# GR_Action_Ascensseur.net
KiCad netlist of a schematic drawn in Altium Designer
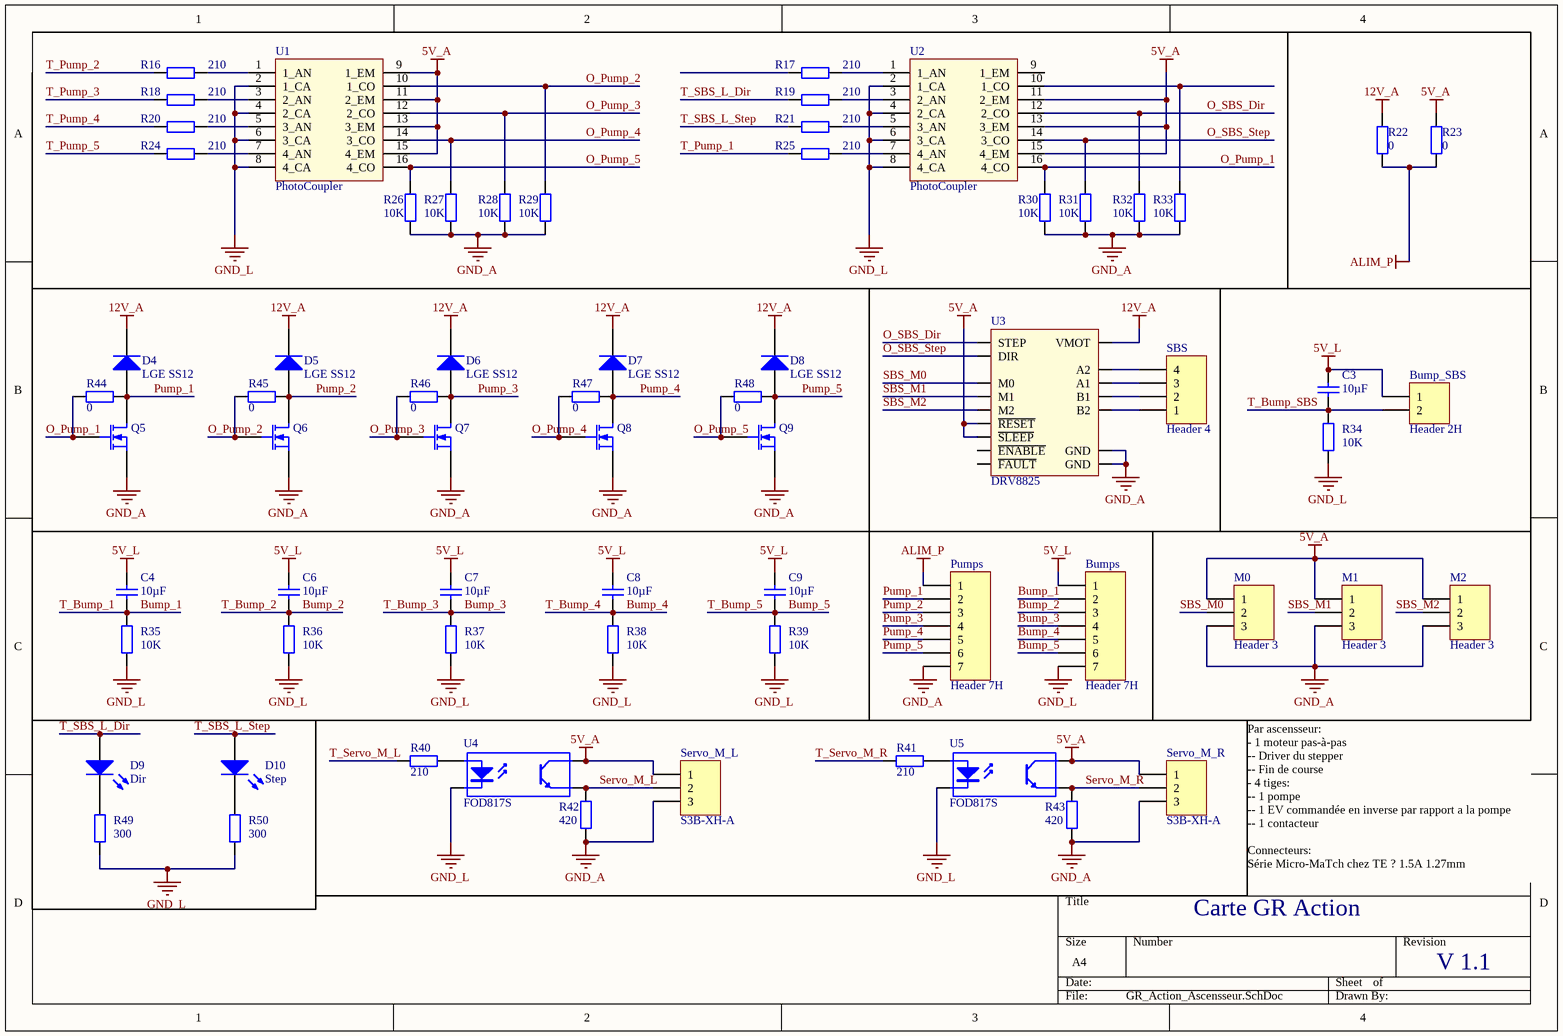
[diagram p0: GR_Action_Ascensseur.SchDoc]

(export (version "E")
  (design (tool "Eeschema 10.0.6"))
  (components
    (comp (ref "Bumps")
      (value "Header 7H")
      (footprint "S7B-XH-A")
      (description "Header, 7-Pin, Right Angle")
      (fields (field (name "PUBLISHER") "Altium Limited"))
      (libsource (lib "Miscellaneous Connectors") (part "Header 7H"))
    )
    (comp (ref "Bump_SBS")
      (value "Header 2H")
      (footprint "S2B-XH-A")
      (description "Header, 2-Pin, Right Angle")
      (fields (field (name "PUBLISHER") "Altium Limited"))
      (libsource (lib "Miscellaneous Connectors") (part "Header 2H"))
    )
    (comp (ref "C3")
      (value "10µF")
      (footprint "Capacitor 1206")
      (description "Capacitor")
      (fields (field (name "PUBLISHER") "Altium Limited"))
      (libsource (lib "Miscellaneous Devices") (part "Cap"))
    )
    (comp (ref "C4")
      (value "10µF")
      (footprint "Capacitor 1206")
      (description "Capacitor")
      (fields (field (name "PUBLISHER") "Altium Limited"))
      (libsource (lib "Miscellaneous Devices") (part "Cap"))
    )
    (comp (ref "C6")
      (value "10µF")
      (footprint "Capacitor 1206")
      (description "Capacitor")
      (fields (field (name "PUBLISHER") "Altium Limited"))
      (libsource (lib "Miscellaneous Devices") (part "Cap"))
    )
    (comp (ref "C7")
      (value "10µF")
      (footprint "Capacitor 1206")
      (description "Capacitor")
      (fields (field (name "PUBLISHER") "Altium Limited"))
      (libsource (lib "Miscellaneous Devices") (part "Cap"))
    )
    (comp (ref "C8")
      (value "10µF")
      (footprint "Capacitor 1206")
      (description "Capacitor")
      (fields (field (name "PUBLISHER") "Altium Limited"))
      (libsource (lib "Miscellaneous Devices") (part "Cap"))
    )
    (comp (ref "C9")
      (value "10µF")
      (footprint "Capacitor 1206")
      (description "Capacitor")
      (fields (field (name "PUBLISHER") "Altium Limited"))
      (libsource (lib "Miscellaneous Devices") (part "Cap"))
    )
    (comp (ref "D4")
      (value "LGE SS12")
      (footprint "SMB")
      (description "Default Diode")
      (fields (field (name "PUBLISHER") "Altium Limited"))
      (libsource (lib "Miscellaneous Devices") (part "Diode"))
    )
    (comp (ref "D5")
      (value "LGE SS12")
      (footprint "SMB")
      (description "Default Diode")
      (fields (field (name "PUBLISHER") "Altium Limited"))
      (libsource (lib "Miscellaneous Devices") (part "Diode"))
    )
    (comp (ref "D6")
      (value "LGE SS12")
      (footprint "SMB")
      (description "Default Diode")
      (fields (field (name "PUBLISHER") "Altium Limited"))
      (libsource (lib "Miscellaneous Devices") (part "Diode"))
    )
    (comp (ref "D7")
      (value "LGE SS12")
      (footprint "SMB")
      (description "Default Diode")
      (fields (field (name "PUBLISHER") "Altium Limited"))
      (libsource (lib "Miscellaneous Devices") (part "Diode"))
    )
    (comp (ref "D8")
      (value "LGE SS12")
      (footprint "SMB")
      (description "Default Diode")
      (fields (field (name "PUBLISHER") "Altium Limited"))
      (libsource (lib "Miscellaneous Devices") (part "Diode"))
    )
    (comp (ref "D9")
      (value "Dir")
      (footprint "KP-3216SEC")
      (description "Typical RED, GREEN, YELLOW, AMBER GaAs LED")
      (fields (field (name "PUBLISHER") "Altium Limited"))
      (libsource (lib "Miscellaneous Devices") (part "LED2"))
    )
    (comp (ref "D10")
      (value "Step")
      (footprint "KP-3216SEC")
      (description "Typical RED, GREEN, YELLOW, AMBER GaAs LED")
      (fields (field (name "PUBLISHER") "Altium Limited"))
      (libsource (lib "Miscellaneous Devices") (part "LED2"))
    )
    (comp (ref "M0")
      (value "Header 3")
      (footprint "HDR1X3")
      (description "Header, 3-Pin")
      (fields (field (name "PUBLISHER") "Altium Limited"))
      (libsource (lib "Miscellaneous Connectors") (part "Header 3"))
    )
    (comp (ref "M1")
      (value "Header 3")
      (footprint "HDR1X3")
      (description "Header, 3-Pin")
      (fields (field (name "PUBLISHER") "Altium Limited"))
      (libsource (lib "Miscellaneous Connectors") (part "Header 3"))
    )
    (comp (ref "M2")
      (value "Header 3")
      (footprint "HDR1X3")
      (description "Header, 3-Pin")
      (fields (field (name "PUBLISHER") "Altium Limited"))
      (libsource (lib "Miscellaneous Connectors") (part "Header 3"))
    )
    (comp (ref "Pumps")
      (value "Header 7H")
      (footprint "S7B-XH-A")
      (description "Header, 7-Pin, Right Angle")
      (fields (field (name "PUBLISHER") "Altium Limited"))
      (libsource (lib "Miscellaneous Connectors") (part "Header 7H"))
    )
    (comp (ref "Q5")
      (value "MOSFET-N")
      (footprint "SOT23_M")
      (description "N-Channel MOSFET")
      (fields (field (name "PUBLISHER") "Altium Limited"))
      (libsource (lib "Miscellaneous Devices") (part "MOSFET-N"))
    )
    (comp (ref "Q6")
      (value "MOSFET-N")
      (footprint "SOT23_M")
      (description "N-Channel MOSFET")
      (fields (field (name "PUBLISHER") "Altium Limited"))
      (libsource (lib "Miscellaneous Devices") (part "MOSFET-N"))
    )
    (comp (ref "Q7")
      (value "MOSFET-N")
      (footprint "SOT23_M")
      (description "N-Channel MOSFET")
      (fields (field (name "PUBLISHER") "Altium Limited"))
      (libsource (lib "Miscellaneous Devices") (part "MOSFET-N"))
    )
    (comp (ref "Q8")
      (value "MOSFET-N")
      (footprint "SOT23_M")
      (description "N-Channel MOSFET")
      (fields (field (name "PUBLISHER") "Altium Limited"))
      (libsource (lib "Miscellaneous Devices") (part "MOSFET-N"))
    )
    (comp (ref "Q9")
      (value "MOSFET-N")
      (footprint "SOT23_M")
      (description "N-Channel MOSFET")
      (fields (field (name "PUBLISHER") "Altium Limited"))
      (libsource (lib "Miscellaneous Devices") (part "MOSFET-N"))
    )
    (comp (ref "R16")
      (value "210")
      (footprint "Resistor 1206")
      (description "Resistor")
      (fields (field (name "Comment") "Res2") (field (name "PUBLISHER") "Altium Limited"))
      (libsource (lib "") (part "Res2_2"))
    )
    (comp (ref "R17")
      (value "210")
      (footprint "Resistor 1206")
      (description "Resistor")
      (fields (field (name "Comment") "Res2") (field (name "PUBLISHER") "Altium Limited"))
      (libsource (lib "") (part "Res2_2"))
    )
    (comp (ref "R18")
      (value "210")
      (footprint "Resistor 1206")
      (description "Resistor")
      (fields (field (name "Comment") "Res2") (field (name "PUBLISHER") "Altium Limited"))
      (libsource (lib "") (part "Res2_2"))
    )
    (comp (ref "R19")
      (value "210")
      (footprint "Resistor 1206")
      (description "Resistor")
      (fields (field (name "Comment") "Res2") (field (name "PUBLISHER") "Altium Limited"))
      (libsource (lib "") (part "Res2_2"))
    )
    (comp (ref "R20")
      (value "210")
      (footprint "Resistor 1206")
      (description "Resistor")
      (fields (field (name "Comment") "Res2") (field (name "PUBLISHER") "Altium Limited"))
      (libsource (lib "") (part "Res2_2"))
    )
    (comp (ref "R21")
      (value "210")
      (footprint "Resistor 1206")
      (description "Resistor")
      (fields (field (name "Comment") "Res2") (field (name "PUBLISHER") "Altium Limited"))
      (libsource (lib "") (part "Res2_2"))
    )
    (comp (ref "R22")
      (value "0")
      (footprint "Resistor 1206")
      (description "Resistor")
      (fields (field (name "Comment") "Res2") (field (name "PUBLISHER") "Altium Limited"))
      (libsource (lib "") (part "Res2_1"))
    )
    (comp (ref "R23")
      (value "0")
      (footprint "Resistor 1206")
      (description "Resistor")
      (fields (field (name "Comment") "Res2") (field (name "PUBLISHER") "Altium Limited"))
      (libsource (lib "") (part "Res2_1"))
    )
    (comp (ref "R24")
      (value "210")
      (footprint "Resistor 1206")
      (description "Resistor")
      (fields (field (name "Comment") "Res2") (field (name "PUBLISHER") "Altium Limited"))
      (libsource (lib "") (part "Res2_2"))
    )
    (comp (ref "R25")
      (value "210")
      (footprint "Resistor 1206")
      (description "Resistor")
      (fields (field (name "Comment") "Res2") (field (name "PUBLISHER") "Altium Limited"))
      (libsource (lib "") (part "Res2_2"))
    )
    (comp (ref "R26")
      (value "10K")
      (footprint "Resistor 1206")
      (description "Resistor")
      (fields (field (name "Comment") "Res2") (field (name "PUBLISHER") "Altium Limited"))
      (libsource (lib "") (part "Res2_3"))
    )
    (comp (ref "R27")
      (value "10K")
      (footprint "Resistor 1206")
      (description "Resistor")
      (fields (field (name "Comment") "Res2") (field (name "PUBLISHER") "Altium Limited"))
      (libsource (lib "") (part "Res2_3"))
    )
    (comp (ref "R28")
      (value "10K")
      (footprint "Resistor 1206")
      (description "Resistor")
      (fields (field (name "Comment") "Res2") (field (name "PUBLISHER") "Altium Limited"))
      (libsource (lib "") (part "Res2_3"))
    )
    (comp (ref "R29")
      (value "10K")
      (footprint "Resistor 1206")
      (description "Resistor")
      (fields (field (name "Comment") "Res2") (field (name "PUBLISHER") "Altium Limited"))
      (libsource (lib "") (part "Res2_3"))
    )
    (comp (ref "R30")
      (value "10K")
      (footprint "Resistor 1206")
      (description "Resistor")
      (fields (field (name "Comment") "Res2") (field (name "PUBLISHER") "Altium Limited"))
      (libsource (lib "") (part "Res2_3"))
    )
    (comp (ref "R31")
      (value "10K")
      (footprint "Resistor 1206")
      (description "Resistor")
      (fields (field (name "Comment") "Res2") (field (name "PUBLISHER") "Altium Limited"))
      (libsource (lib "") (part "Res2_3"))
    )
    (comp (ref "R32")
      (value "10K")
      (footprint "Resistor 1206")
      (description "Resistor")
      (fields (field (name "Comment") "Res2") (field (name "PUBLISHER") "Altium Limited"))
      (libsource (lib "") (part "Res2_3"))
    )
    (comp (ref "R33")
      (value "10K")
      (footprint "Resistor 1206")
      (description "Resistor")
      (fields (field (name "Comment") "Res2") (field (name "PUBLISHER") "Altium Limited"))
      (libsource (lib "") (part "Res2_3"))
    )
    (comp (ref "R34")
      (value "10K")
      (footprint "Resistor 1206")
      (description "Resistor")
      (fields (field (name "Comment") "Res2") (field (name "PUBLISHER") "Altium Limited"))
      (libsource (lib "") (part "Res2_3"))
    )
    (comp (ref "R35")
      (value "10K")
      (footprint "Resistor 1206")
      (description "Resistor")
      (fields (field (name "Comment") "Res2") (field (name "PUBLISHER") "Altium Limited"))
      (libsource (lib "") (part "Res2_3"))
    )
    (comp (ref "R36")
      (value "10K")
      (footprint "Resistor 1206")
      (description "Resistor")
      (fields (field (name "Comment") "Res2") (field (name "PUBLISHER") "Altium Limited"))
      (libsource (lib "") (part "Res2_3"))
    )
    (comp (ref "R37")
      (value "10K")
      (footprint "Resistor 1206")
      (description "Resistor")
      (fields (field (name "Comment") "Res2") (field (name "PUBLISHER") "Altium Limited"))
      (libsource (lib "") (part "Res2_3"))
    )
    (comp (ref "R38")
      (value "10K")
      (footprint "Resistor 1206")
      (description "Resistor")
      (fields (field (name "Comment") "Res2") (field (name "PUBLISHER") "Altium Limited"))
      (libsource (lib "") (part "Res2_3"))
    )
    (comp (ref "R39")
      (value "10K")
      (footprint "Resistor 1206")
      (description "Resistor")
      (fields (field (name "Comment") "Res2") (field (name "PUBLISHER") "Altium Limited"))
      (libsource (lib "") (part "Res2_3"))
    )
    (comp (ref "R40")
      (value "210")
      (footprint "Resistor 1206")
      (description "Resistor")
      (fields (field (name "Comment") "Res2") (field (name "PUBLISHER") "Altium Limited"))
      (libsource (lib "") (part "Res2_2"))
    )
    (comp (ref "R41")
      (value "210")
      (footprint "Resistor 1206")
      (description "Resistor")
      (fields (field (name "Comment") "Res2") (field (name "PUBLISHER") "Altium Limited"))
      (libsource (lib "") (part "Res2_2"))
    )
    (comp (ref "R42")
      (value "420")
      (footprint "Resistor 1206")
      (description "Resistor")
      (fields (field (name "Comment") "Res2") (field (name "PUBLISHER") "Altium Limited"))
      (libsource (lib "") (part "Res2_3"))
    )
    (comp (ref "R43")
      (value "420")
      (footprint "Resistor 1206")
      (description "Resistor")
      (fields (field (name "Comment") "Res2") (field (name "PUBLISHER") "Altium Limited"))
      (libsource (lib "") (part "Res2_3"))
    )
    (comp (ref "R44")
      (value "0")
      (footprint "Resistor 1206")
      (description "Resistor")
      (fields (field (name "Comment") "Res2") (field (name "PUBLISHER") "Altium Limited"))
      (libsource (lib "Miscellaneous Devices") (part "Res2"))
    )
    (comp (ref "R45")
      (value "0")
      (footprint "Resistor 1206")
      (description "Resistor")
      (fields (field (name "Comment") "Res2") (field (name "PUBLISHER") "Altium Limited"))
      (libsource (lib "Miscellaneous Devices") (part "Res2"))
    )
    (comp (ref "R46")
      (value "0")
      (footprint "Resistor 1206")
      (description "Resistor")
      (fields (field (name "Comment") "Res2") (field (name "PUBLISHER") "Altium Limited"))
      (libsource (lib "Miscellaneous Devices") (part "Res2"))
    )
    (comp (ref "R47")
      (value "0")
      (footprint "Resistor 1206")
      (description "Resistor")
      (fields (field (name "Comment") "Res2") (field (name "PUBLISHER") "Altium Limited"))
      (libsource (lib "Miscellaneous Devices") (part "Res2"))
    )
    (comp (ref "R48")
      (value "0")
      (footprint "Resistor 1206")
      (description "Resistor")
      (fields (field (name "Comment") "Res2") (field (name "PUBLISHER") "Altium Limited"))
      (libsource (lib "Miscellaneous Devices") (part "Res2"))
    )
    (comp (ref "R49")
      (value "300")
      (footprint "Resistor 1206")
      (description "Resistor")
      (fields (field (name "Comment") "Res2") (field (name "PUBLISHER") "Altium Limited"))
      (libsource (lib "") (part "Res2_3"))
    )
    (comp (ref "R50")
      (value "300")
      (footprint "Resistor 1206")
      (description "Resistor")
      (fields (field (name "Comment") "Res2") (field (name "PUBLISHER") "Altium Limited"))
      (libsource (lib "") (part "Res2_3"))
    )
    (comp (ref "SBS")
      (value "Header 4")
      (footprint "S4B-XH-A")
      (description "Header, 4-Pin")
      (fields (field (name "PUBLISHER") "Altium Limited"))
      (libsource (lib "Miscellaneous Connectors") (part "Header 4"))
    )
    (comp (ref "Servo_M_L")
      (value "S3B-XH-A")
      (footprint "S3B-XH-A")
      (description "Header, 3-Pin, Right Angle")
      (fields (field (name "PUBLISHER") "Altium Limited"))
      (libsource (lib "Miscellaneous Connectors") (part "Header 3H"))
    )
    (comp (ref "Servo_M_R")
      (value "S3B-XH-A")
      (footprint "S3B-XH-A")
      (description "Header, 3-Pin, Right Angle")
      (fields (field (name "PUBLISHER") "Altium Limited"))
      (libsource (lib "Miscellaneous Connectors") (part "Header 3H"))
    )
    (comp (ref "U1")
      (value "PhotoCoupler")
      (footprint "LTV-247")
      (description "Integrated Circuit")
      (fields
        (field (name "MANUFACTURER_PART_NUMBER") "LTV-247")
        (field (name "MOUSER PART NUMBER") "859-LTV-247")
      )
      (libsource (lib "SamacSys") (part "LTV-247"))
    )
    (comp (ref "U2")
      (value "PhotoCoupler")
      (footprint "LTV-247")
      (description "Integrated Circuit")
      (fields
        (field (name "MANUFACTURER_PART_NUMBER") "LTV-247")
        (field (name "MOUSER PART NUMBER") "859-LTV-247")
      )
      (libsource (lib "SamacSys") (part "LTV-247"))
    )
    (comp (ref "U3")
      (value "DRV8825")
      (footprint "DRV8825")
      (description "Stepper Driver Module")
      (libsource (lib "SupaeroRobot") (part "DRV8825"))
    )
    (comp (ref "U4")
      (value "FOD817S")
      (footprint "SOP254P1016X385-4N")
      (description "4-Pin Phototransistor Optocoupler")
      (fields (field (name "PUBLISHER") "Altium Limited"))
      (libsource (lib "Miscellaneous Devices") (part "Optoisolator1"))
    )
    (comp (ref "U5")
      (value "FOD817S")
      (footprint "SOP254P1016X385-4N")
      (description "4-Pin Phototransistor Optocoupler")
      (fields (field (name "PUBLISHER") "Altium Limited"))
      (libsource (lib "Miscellaneous Devices") (part "Optoisolator1"))
    )
  )
  (nets
    (net (code "1") (name "/Bump_1") (class "Default")
      (node (ref "Bumps") (pin "2") (pinfunction "2_2") (pintype "passive"))
      (node (ref "C4") (pin "1") (pinfunction "1_1") (pintype "passive"))
      (node (ref "R35") (pin "2") (pinfunction "2_2") (pintype "passive"))
    )
    (net (code "2") (name "/Bump_2") (class "Default")
      (node (ref "Bumps") (pin "3") (pinfunction "3_3") (pintype "passive"))
      (node (ref "C6") (pin "1") (pinfunction "1_1") (pintype "passive"))
      (node (ref "R36") (pin "2") (pinfunction "2_2") (pintype "passive"))
    )
    (net (code "3") (name "/Bump_3") (class "Default")
      (node (ref "Bumps") (pin "4") (pinfunction "4_4") (pintype "passive"))
      (node (ref "C7") (pin "1") (pinfunction "1_1") (pintype "passive"))
      (node (ref "R37") (pin "2") (pinfunction "2_2") (pintype "passive"))
    )
    (net (code "4") (name "/Bump_4") (class "Default")
      (node (ref "Bumps") (pin "5") (pinfunction "5_5") (pintype "passive"))
      (node (ref "C8") (pin "1") (pinfunction "1_1") (pintype "passive"))
      (node (ref "R38") (pin "2") (pinfunction "2_2") (pintype "passive"))
    )
    (net (code "5") (name "/Bump_5") (class "Default")
      (node (ref "Bumps") (pin "6") (pinfunction "6_6") (pintype "passive"))
      (node (ref "C9") (pin "1") (pinfunction "1_1") (pintype "passive"))
      (node (ref "R39") (pin "2") (pinfunction "2_2") (pintype "passive"))
    )
    (net (code "6") (name "/O_Pump_1") (class "Default")
      (node (ref "Q5") (pin "2") (pinfunction "G_2") (pintype "passive"))
      (node (ref "R30") (pin "2") (pinfunction "2_2") (pintype "passive"))
      (node (ref "R44") (pin "1") (pinfunction "1_1") (pintype "passive"))
      (node (ref "U2") (pin "16") (pinfunction "4_CO_16") (pintype "passive"))
    )
    (net (code "7") (name "/O_Pump_2") (class "Default")
      (node (ref "Q6") (pin "2") (pinfunction "G_2") (pintype "passive"))
      (node (ref "R29") (pin "2") (pinfunction "2_2") (pintype "passive"))
      (node (ref "R45") (pin "1") (pinfunction "1_1") (pintype "passive"))
      (node (ref "U1") (pin "10") (pinfunction "1_CO_10") (pintype "passive"))
    )
    (net (code "8") (name "/O_Pump_3") (class "Default")
      (node (ref "Q7") (pin "2") (pinfunction "G_2") (pintype "passive"))
      (node (ref "R28") (pin "2") (pinfunction "2_2") (pintype "passive"))
      (node (ref "R46") (pin "1") (pinfunction "1_1") (pintype "passive"))
      (node (ref "U1") (pin "12") (pinfunction "2_CO_12") (pintype "passive"))
    )
    (net (code "9") (name "/O_Pump_4") (class "Default")
      (node (ref "Q8") (pin "2") (pinfunction "G_2") (pintype "passive"))
      (node (ref "R27") (pin "2") (pinfunction "2_2") (pintype "passive"))
      (node (ref "R47") (pin "1") (pinfunction "1_1") (pintype "passive"))
      (node (ref "U1") (pin "14") (pinfunction "3_CO_14") (pintype "passive"))
    )
    (net (code "10") (name "/O_Pump_5") (class "Default")
      (node (ref "Q9") (pin "2") (pinfunction "G_2") (pintype "passive"))
      (node (ref "R26") (pin "2") (pinfunction "2_2") (pintype "passive"))
      (node (ref "R48") (pin "1") (pinfunction "1_1") (pintype "passive"))
      (node (ref "U1") (pin "16") (pinfunction "4_CO_16") (pintype "passive"))
    )
    (net (code "11") (name "/O_SBS_Dir") (class "Default")
      (node (ref "R32") (pin "2") (pinfunction "2_2") (pintype "passive"))
      (node (ref "U2") (pin "12") (pinfunction "2_CO_12") (pintype "passive"))
      (node (ref "U3") (pin "7") (pinfunction "STEP_7") (pintype "passive"))
    )
    (net (code "12") (name "/O_SBS_Step") (class "Default")
      (node (ref "R31") (pin "2") (pinfunction "2_2") (pintype "passive"))
      (node (ref "U2") (pin "14") (pinfunction "3_CO_14") (pintype "passive"))
      (node (ref "U3") (pin "8") (pinfunction "DIR_8") (pintype "passive"))
    )
    (net (code "13") (name "/Pump_1") (class "Default")
      (node (ref "D4") (pin "1") (pinfunction "A_1") (pintype "passive"))
      (node (ref "Pumps") (pin "2") (pinfunction "2_2") (pintype "passive"))
      (node (ref "Q5") (pin "1") (pinfunction "D_1") (pintype "passive"))
      (node (ref "R44") (pin "2") (pinfunction "2_2") (pintype "passive"))
    )
    (net (code "14") (name "/Pump_2") (class "Default")
      (node (ref "D5") (pin "1") (pinfunction "A_1") (pintype "passive"))
      (node (ref "Pumps") (pin "3") (pinfunction "3_3") (pintype "passive"))
      (node (ref "Q6") (pin "1") (pinfunction "D_1") (pintype "passive"))
      (node (ref "R45") (pin "2") (pinfunction "2_2") (pintype "passive"))
    )
    (net (code "15") (name "/Pump_3") (class "Default")
      (node (ref "D6") (pin "1") (pinfunction "A_1") (pintype "passive"))
      (node (ref "Pumps") (pin "4") (pinfunction "4_4") (pintype "passive"))
      (node (ref "Q7") (pin "1") (pinfunction "D_1") (pintype "passive"))
      (node (ref "R46") (pin "2") (pinfunction "2_2") (pintype "passive"))
    )
    (net (code "16") (name "/Pump_4") (class "Default")
      (node (ref "D7") (pin "1") (pinfunction "A_1") (pintype "passive"))
      (node (ref "Pumps") (pin "5") (pinfunction "5_5") (pintype "passive"))
      (node (ref "Q8") (pin "1") (pinfunction "D_1") (pintype "passive"))
      (node (ref "R47") (pin "2") (pinfunction "2_2") (pintype "passive"))
    )
    (net (code "17") (name "/Pump_5") (class "Default")
      (node (ref "D8") (pin "1") (pinfunction "A_1") (pintype "passive"))
      (node (ref "Pumps") (pin "6") (pinfunction "6_6") (pintype "passive"))
      (node (ref "Q9") (pin "1") (pinfunction "D_1") (pintype "passive"))
      (node (ref "R48") (pin "2") (pinfunction "2_2") (pintype "passive"))
    )
    (net (code "18") (name "/SBS_M0") (class "Default")
      (node (ref "M0") (pin "2") (pinfunction "2_2") (pintype "passive"))
      (node (ref "U3") (pin "2") (pinfunction "M0_2") (pintype "passive"))
    )
    (net (code "19") (name "/SBS_M1") (class "Default")
      (node (ref "M1") (pin "2") (pinfunction "2_2") (pintype "passive"))
      (node (ref "U3") (pin "3") (pinfunction "M1_3") (pintype "passive"))
    )
    (net (code "20") (name "/SBS_M2") (class "Default")
      (node (ref "M2") (pin "2") (pinfunction "2_2") (pintype "passive"))
      (node (ref "U3") (pin "4") (pinfunction "M2_4") (pintype "passive"))
    )
    (net (code "21") (name "/Servo_M_L") (class "Default")
      (node (ref "R42") (pin "2") (pinfunction "2_2") (pintype "passive"))
      (node (ref "Servo_M_L") (pin "2") (pinfunction "2_2") (pintype "passive"))
      (node (ref "U4") (pin "3") (pinfunction "E_3") (pintype "passive"))
    )
    (net (code "22") (name "/Servo_M_R") (class "Default")
      (node (ref "R43") (pin "2") (pinfunction "2_2") (pintype "passive"))
      (node (ref "Servo_M_R") (pin "2") (pinfunction "2_2") (pintype "passive"))
      (node (ref "U5") (pin "3") (pinfunction "E_3") (pintype "passive"))
    )
    (net (code "23") (name "/T_Bump_SBS") (class "Default")
      (node (ref "Bump_SBS") (pin "2") (pinfunction "2_2") (pintype "passive"))
      (node (ref "C3") (pin "1") (pinfunction "1_1") (pintype "passive"))
      (node (ref "R34") (pin "2") (pinfunction "2_2") (pintype "passive"))
    )
    (net (code "24") (name "/T_Pump_1") (class "Default")
      (node (ref "R25") (pin "2") (pinfunction "2_2") (pintype "passive"))
    )
    (net (code "25") (name "/T_Pump_2") (class "Default")
      (node (ref "R16") (pin "2") (pinfunction "2_2") (pintype "passive"))
    )
    (net (code "26") (name "/T_Pump_3") (class "Default")
      (node (ref "R18") (pin "2") (pinfunction "2_2") (pintype "passive"))
    )
    (net (code "27") (name "/T_Pump_4") (class "Default")
      (node (ref "R20") (pin "2") (pinfunction "2_2") (pintype "passive"))
    )
    (net (code "28") (name "/T_Pump_5") (class "Default")
      (node (ref "R24") (pin "2") (pinfunction "2_2") (pintype "passive"))
    )
    (net (code "29") (name "/T_SBS_L_Dir") (class "Default")
      (node (ref "D9") (pin "1") (pinfunction "A_1") (pintype "passive"))
      (node (ref "R19") (pin "2") (pinfunction "2_2") (pintype "passive"))
    )
    (net (code "30") (name "/T_SBS_L_Step") (class "Default")
      (node (ref "D10") (pin "1") (pinfunction "A_1") (pintype "passive"))
      (node (ref "R21") (pin "2") (pinfunction "2_2") (pintype "passive"))
    )
    (net (code "31") (name "/T_Servo_M_L") (class "Default")
      (node (ref "R40") (pin "2") (pinfunction "2_2") (pintype "passive"))
    )
    (net (code "32") (name "/T_Servo_M_R") (class "Default")
      (node (ref "R41") (pin "2") (pinfunction "2_2") (pintype "passive"))
    )
    (net (code "33") (name "5V_A") (class "Default")
      (node (ref "M0") (pin "1") (pinfunction "1_1") (pintype "passive"))
      (node (ref "M1") (pin "1") (pinfunction "1_1") (pintype "passive"))
      (node (ref "M2") (pin "1") (pinfunction "1_1") (pintype "passive"))
      (node (ref "R23") (pin "1") (pinfunction "1_1") (pintype "passive"))
      (node (ref "Servo_M_L") (pin "1") (pinfunction "1_1") (pintype "passive"))
      (node (ref "Servo_M_R") (pin "1") (pinfunction "1_1") (pintype "passive"))
      (node (ref "U1") (pin "11") (pinfunction "2_EM_11") (pintype "passive"))
      (node (ref "U1") (pin "13") (pinfunction "3_EM_13") (pintype "passive"))
      (node (ref "U1") (pin "15") (pinfunction "4_EM_15") (pintype "passive"))
      (node (ref "U1") (pin "9") (pinfunction "1_EM_9") (pintype "passive"))
      (node (ref "U2") (pin "11") (pinfunction "2_EM_11") (pintype "passive"))
      (node (ref "U2") (pin "13") (pinfunction "3_EM_13") (pintype "passive"))
      (node (ref "U2") (pin "15") (pinfunction "4_EM_15") (pintype "passive"))
      (node (ref "U3") (pin "5") (pinfunction "~{RESET}_5") (pintype "passive"))
      (node (ref "U3") (pin "6") (pinfunction "~{SLEEP}_6") (pintype "passive"))
      (node (ref "U4") (pin "4") (pinfunction "C_4") (pintype "passive"))
      (node (ref "U5") (pin "4") (pinfunction "C_4") (pintype "passive"))
    )
    (net (code "34") (name "5V_L") (class "Default")
      (node (ref "Bump_SBS") (pin "1") (pinfunction "1_1") (pintype "passive"))
      (node (ref "Bumps") (pin "1") (pinfunction "1_1") (pintype "passive"))
      (node (ref "C3") (pin "2") (pinfunction "2_2") (pintype "passive"))
      (node (ref "C4") (pin "2") (pinfunction "2_2") (pintype "passive"))
      (node (ref "C6") (pin "2") (pinfunction "2_2") (pintype "passive"))
      (node (ref "C7") (pin "2") (pinfunction "2_2") (pintype "passive"))
      (node (ref "C8") (pin "2") (pinfunction "2_2") (pintype "passive"))
      (node (ref "C9") (pin "2") (pinfunction "2_2") (pintype "passive"))
    )
    (net (code "35") (name "12V_A") (class "Default")
      (node (ref "D4") (pin "2") (pinfunction "K_2") (pintype "passive"))
      (node (ref "D5") (pin "2") (pinfunction "K_2") (pintype "passive"))
      (node (ref "D6") (pin "2") (pinfunction "K_2") (pintype "passive"))
      (node (ref "D7") (pin "2") (pinfunction "K_2") (pintype "passive"))
      (node (ref "D8") (pin "2") (pinfunction "K_2") (pintype "passive"))
      (node (ref "R22") (pin "1") (pinfunction "1_1") (pintype "passive"))
      (node (ref "U3") (pin "16") (pinfunction "VMOT_16") (pintype "passive"))
    )
    (net (code "36") (name "ALIM_P") (class "Default")
      (node (ref "Pumps") (pin "1") (pinfunction "1_1") (pintype "passive"))
      (node (ref "R22") (pin "2") (pinfunction "2_2") (pintype "passive"))
      (node (ref "R23") (pin "2") (pinfunction "2_2") (pintype "passive"))
    )
    (net (code "37") (name "GND_A") (class "Default")
      (node (ref "M0") (pin "3") (pinfunction "3_3") (pintype "passive"))
      (node (ref "M1") (pin "3") (pinfunction "3_3") (pintype "passive"))
      (node (ref "M2") (pin "3") (pinfunction "3_3") (pintype "passive"))
      (node (ref "Pumps") (pin "7") (pinfunction "7_7") (pintype "passive"))
      (node (ref "Q5") (pin "3") (pinfunction "S_3") (pintype "passive"))
      (node (ref "Q6") (pin "3") (pinfunction "S_3") (pintype "passive"))
      (node (ref "Q7") (pin "3") (pinfunction "S_3") (pintype "passive"))
      (node (ref "Q8") (pin "3") (pinfunction "S_3") (pintype "passive"))
      (node (ref "Q9") (pin "3") (pinfunction "S_3") (pintype "passive"))
      (node (ref "R26") (pin "1") (pinfunction "1_1") (pintype "passive"))
      (node (ref "R27") (pin "1") (pinfunction "1_1") (pintype "passive"))
      (node (ref "R28") (pin "1") (pinfunction "1_1") (pintype "passive"))
      (node (ref "R29") (pin "1") (pinfunction "1_1") (pintype "passive"))
      (node (ref "R30") (pin "1") (pinfunction "1_1") (pintype "passive"))
      (node (ref "R31") (pin "1") (pinfunction "1_1") (pintype "passive"))
      (node (ref "R32") (pin "1") (pinfunction "1_1") (pintype "passive"))
      (node (ref "R33") (pin "1") (pinfunction "1_1") (pintype "passive"))
      (node (ref "R42") (pin "1") (pinfunction "1_1") (pintype "passive"))
      (node (ref "R43") (pin "1") (pinfunction "1_1") (pintype "passive"))
      (node (ref "Servo_M_L") (pin "3") (pinfunction "3_3") (pintype "passive"))
      (node (ref "Servo_M_R") (pin "3") (pinfunction "3_3") (pintype "passive"))
      (node (ref "U3") (pin "15") (pinfunction "GND_15") (pintype "passive"))
      (node (ref "U3") (pin "9") (pinfunction "GND_9") (pintype "passive"))
    )
    (net (code "38") (name "GND_L") (class "Default")
      (node (ref "Bumps") (pin "7") (pinfunction "7_7") (pintype "passive"))
      (node (ref "R34") (pin "1") (pinfunction "1_1") (pintype "passive"))
      (node (ref "R35") (pin "1") (pinfunction "1_1") (pintype "passive"))
      (node (ref "R36") (pin "1") (pinfunction "1_1") (pintype "passive"))
      (node (ref "R37") (pin "1") (pinfunction "1_1") (pintype "passive"))
      (node (ref "R38") (pin "1") (pinfunction "1_1") (pintype "passive"))
      (node (ref "R39") (pin "1") (pinfunction "1_1") (pintype "passive"))
      (node (ref "R49") (pin "1") (pinfunction "1_1") (pintype "passive"))
      (node (ref "R50") (pin "1") (pinfunction "1_1") (pintype "passive"))
      (node (ref "U1") (pin "2") (pinfunction "1_CA_2") (pintype "passive"))
      (node (ref "U1") (pin "4") (pinfunction "2_CA_4") (pintype "passive"))
      (node (ref "U1") (pin "6") (pinfunction "3_CA_6") (pintype "passive"))
      (node (ref "U1") (pin "8") (pinfunction "4_CA_8") (pintype "passive"))
      (node (ref "U2") (pin "2") (pinfunction "1_CA_2") (pintype "passive"))
      (node (ref "U2") (pin "4") (pinfunction "2_CA_4") (pintype "passive"))
      (node (ref "U2") (pin "6") (pinfunction "3_CA_6") (pintype "passive"))
      (node (ref "U2") (pin "8") (pinfunction "4_CA_8") (pintype "passive"))
      (node (ref "U4") (pin "2") (pinfunction "K_2") (pintype "passive"))
      (node (ref "U5") (pin "2") (pinfunction "K_2") (pintype "passive"))
    )
    (net (code "39") (name "Net-(D9-K)") (class "Default")
      (node (ref "D9") (pin "2") (pinfunction "K_2") (pintype "passive"))
      (node (ref "R49") (pin "2") (pinfunction "2_2") (pintype "passive"))
    )
    (net (code "40") (name "Net-(D10-K)") (class "Default")
      (node (ref "D10") (pin "2") (pinfunction "K_2") (pintype "passive"))
      (node (ref "R50") (pin "2") (pinfunction "2_2") (pintype "passive"))
    )
    (net (code "41") (name "Net-(U1-1_AN)") (class "Default")
      (node (ref "R16") (pin "1") (pinfunction "1_1") (pintype "passive"))
      (node (ref "U1") (pin "1") (pinfunction "1_AN_1") (pintype "passive"))
    )
    (net (code "42") (name "Net-(U1-2_AN)") (class "Default")
      (node (ref "R18") (pin "1") (pinfunction "1_1") (pintype "passive"))
      (node (ref "U1") (pin "3") (pinfunction "2_AN_3") (pintype "passive"))
    )
    (net (code "43") (name "Net-(U1-3_AN)") (class "Default")
      (node (ref "R20") (pin "1") (pinfunction "1_1") (pintype "passive"))
      (node (ref "U1") (pin "5") (pinfunction "3_AN_5") (pintype "passive"))
    )
    (net (code "44") (name "Net-(U1-4_AN)") (class "Default")
      (node (ref "R24") (pin "1") (pinfunction "1_1") (pintype "passive"))
      (node (ref "U1") (pin "7") (pinfunction "4_AN_7") (pintype "passive"))
    )
    (net (code "45") (name "Net-(U2-1_AN)") (class "Default")
      (node (ref "R17") (pin "1") (pinfunction "1_1") (pintype "passive"))
      (node (ref "U2") (pin "1") (pinfunction "1_AN_1") (pintype "passive"))
    )
    (net (code "46") (name "Net-(U2-1_CO)") (class "Default")
      (node (ref "R33") (pin "2") (pinfunction "2_2") (pintype "passive"))
      (node (ref "U2") (pin "10") (pinfunction "1_CO_10") (pintype "passive"))
    )
    (net (code "47") (name "Net-(U2-2_AN)") (class "Default")
      (node (ref "R19") (pin "1") (pinfunction "1_1") (pintype "passive"))
      (node (ref "U2") (pin "3") (pinfunction "2_AN_3") (pintype "passive"))
    )
    (net (code "48") (name "Net-(U2-3_AN)") (class "Default")
      (node (ref "R21") (pin "1") (pinfunction "1_1") (pintype "passive"))
      (node (ref "U2") (pin "5") (pinfunction "3_AN_5") (pintype "passive"))
    )
    (net (code "49") (name "Net-(U2-4_AN)") (class "Default")
      (node (ref "R25") (pin "1") (pinfunction "1_1") (pintype "passive"))
      (node (ref "U2") (pin "7") (pinfunction "4_AN_7") (pintype "passive"))
    )
    (net (code "50") (name "Net-(U3-A1)") (class "Default")
      (node (ref "SBS") (pin "3") (pinfunction "3_3") (pintype "passive"))
      (node (ref "U3") (pin "12") (pinfunction "A1_12") (pintype "passive"))
    )
    (net (code "51") (name "Net-(U3-A2)") (class "Default")
      (node (ref "SBS") (pin "4") (pinfunction "4_4") (pintype "passive"))
      (node (ref "U3") (pin "11") (pinfunction "A2_11") (pintype "passive"))
    )
    (net (code "52") (name "Net-(U3-B1)") (class "Default")
      (node (ref "SBS") (pin "2") (pinfunction "2_2") (pintype "passive"))
      (node (ref "U3") (pin "13") (pinfunction "B1_13") (pintype "passive"))
    )
    (net (code "53") (name "Net-(U3-B2)") (class "Default")
      (node (ref "SBS") (pin "1") (pinfunction "1_1") (pintype "passive"))
      (node (ref "U3") (pin "14") (pinfunction "B2_14") (pintype "passive"))
    )
    (net (code "54") (name "Net-(U4-A)") (class "Default")
      (node (ref "R40") (pin "1") (pinfunction "1_1") (pintype "passive"))
      (node (ref "U4") (pin "1") (pinfunction "A_1") (pintype "passive"))
    )
    (net (code "55") (name "Net-(U5-A)") (class "Default")
      (node (ref "R41") (pin "1") (pinfunction "1_1") (pintype "passive"))
      (node (ref "U5") (pin "1") (pinfunction "A_1") (pintype "passive"))
    )
    (net (code "56") (name "unconnected-(R17-Pad2)") (class "Default")
      (node (ref "R17") (pin "2") (pinfunction "2_2") (pintype "passive"))
    )
    (net (code "57") (name "unconnected-(U2-1_EM-Pad9)") (class "Default")
      (node (ref "U2") (pin "9") (pinfunction "1_EM_9") (pintype "passive"))
    )
    (net (code "58") (name "unconnected-(U3-~{ENABLE}-Pad1)") (class "Default")
      (node (ref "U3") (pin "1") (pinfunction "~{ENABLE}_1") (pintype "passive"))
    )
    (net (code "59") (name "unconnected-(U3-~{FAULT}-Pad10)") (class "Default")
      (node (ref "U3") (pin "10") (pinfunction "~{FAULT}_10") (pintype "passive"))
    )
  )
)
